# front_end_block.net
KiCad netlist of a schematic drawn in EAGLE
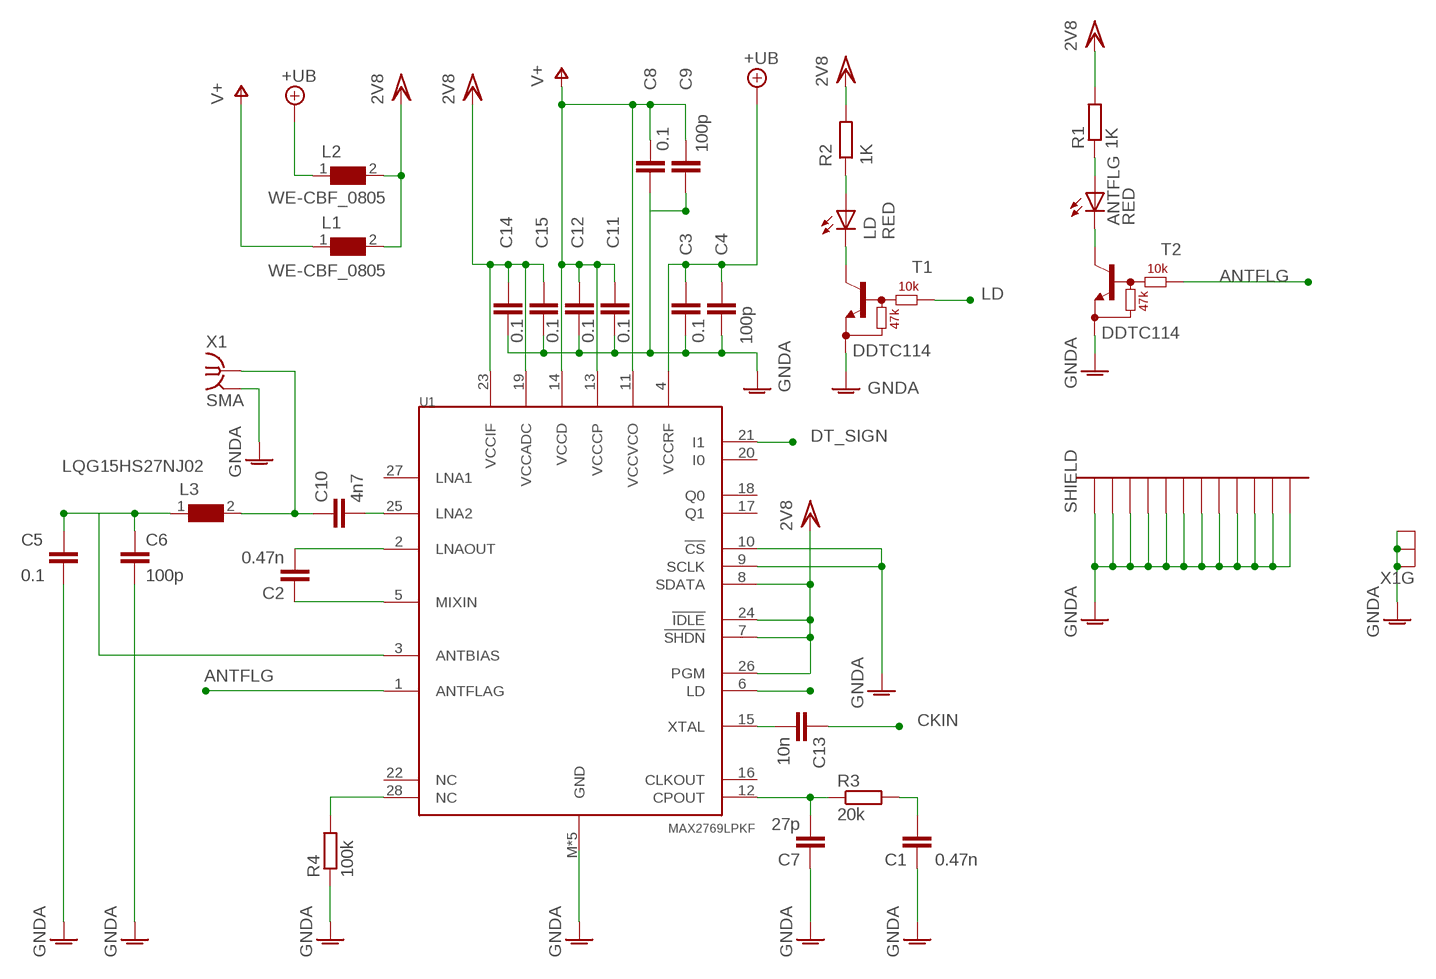
[diagram p0: schematic, sheet 1]

(export (version "E")
  (design (tool "Eeschema 10.0.6"))
  (components
    (comp (ref "ANTFLG")
      (value "RED")
      (footprint "eagle-import:CHIP-LED0603")
      (libsource (lib "eagle-import") (part "LEDCHIP-LED0603"))
    )
    (comp (ref "C1")
      (value "0.47n")
      (footprint "eagle-import:C0603")
      (libsource (lib "eagle-import") (part "rcl_1_C-EUC0603"))
    )
    (comp (ref "C2")
      (value "0.47n")
      (footprint "eagle-import:C0402")
      (libsource (lib "eagle-import") (part "rcl_1_C-EUC0402"))
    )
    (comp (ref "C3")
      (value "0.1")
      (footprint "eagle-import:C0402")
      (libsource (lib "eagle-import") (part "rcl_1_C-EUC0402"))
    )
    (comp (ref "C4")
      (value "100p")
      (footprint "eagle-import:C0402")
      (libsource (lib "eagle-import") (part "rcl_1_C-EUC0402"))
    )
    (comp (ref "C5")
      (value "0.1")
      (footprint "eagle-import:C0603")
      (libsource (lib "eagle-import") (part "C-EUC0603"))
    )
    (comp (ref "C6")
      (value "100p")
      (footprint "eagle-import:C0402")
      (libsource (lib "eagle-import") (part "rcl_1_C-EUC0402"))
    )
    (comp (ref "C7")
      (value "27p")
      (footprint "eagle-import:C0402")
      (libsource (lib "eagle-import") (part "rcl_1_C-EUC0402"))
    )
    (comp (ref "C8")
      (value "0.1")
      (footprint "eagle-import:C0402")
      (libsource (lib "eagle-import") (part "rcl_1_C-EUC0402"))
    )
    (comp (ref "C9")
      (value "100p")
      (footprint "eagle-import:C0402")
      (libsource (lib "eagle-import") (part "rcl_1_C-EUC0402"))
    )
    (comp (ref "C10")
      (value "4n7")
      (footprint "eagle-import:C0402")
      (libsource (lib "eagle-import") (part "rcl_1_C-EUC0402"))
    )
    (comp (ref "C11")
      (value "0.1")
      (footprint "eagle-import:C0402")
      (libsource (lib "eagle-import") (part "rcl_1_C-EUC0402"))
    )
    (comp (ref "C12")
      (value "0.1")
      (footprint "eagle-import:C0402")
      (libsource (lib "eagle-import") (part "rcl_1_C-EUC0402"))
    )
    (comp (ref "C13")
      (value "10n")
      (footprint "eagle-import:C0402")
      (libsource (lib "eagle-import") (part "rcl_1_C-EUC0402"))
    )
    (comp (ref "C14")
      (value "0.1")
      (footprint "eagle-import:C0603")
      (libsource (lib "eagle-import") (part "rcl_1_C-EUC0603"))
    )
    (comp (ref "C15")
      (value "0.1")
      (footprint "eagle-import:C0402")
      (libsource (lib "eagle-import") (part "rcl_1_C-EUC0402"))
    )
    (comp (ref "L1")
      (value "WE-CBF_0805")
      (footprint "eagle-import:0805")
      (libsource (lib "eagle-import") (part "WE-CBF_0805"))
    )
    (comp (ref "L2")
      (value "WE-CBF_0805")
      (footprint "eagle-import:0805")
      (libsource (lib "eagle-import") (part "WE-CBF_0805"))
    )
    (comp (ref "L3")
      (value "LQG15HS27NJ02")
      (footprint "eagle-import:0402")
      (libsource (lib "eagle-import") (part "WE-MK_0402"))
    )
    (comp (ref "LD")
      (value "RED")
      (footprint "eagle-import:CHIP-LED0603")
      (libsource (lib "eagle-import") (part "LEDCHIP-LED0603"))
    )
    (comp (ref "R1")
      (value "1K")
      (footprint "eagle-import:R0402")
      (libsource (lib "eagle-import") (part "R-EU_R0402"))
    )
    (comp (ref "R2")
      (value "1K")
      (footprint "eagle-import:R0402")
      (libsource (lib "eagle-import") (part "R-EU_R0402"))
    )
    (comp (ref "R3")
      (value "20k")
      (footprint "eagle-import:R0402")
      (libsource (lib "eagle-import") (part "R-EU_R0402"))
    )
    (comp (ref "R4")
      (value "100k")
      (footprint "eagle-import:R0402")
      (libsource (lib "eagle-import") (part "R-EU_R0402"))
    )
    (comp (ref "S2")
      (value "BMIS-202")
      (footprint "eagle-import:BMIS-202")
      (libsource (lib "eagle-import") (part "BMIS-202"))
    )
    (comp (ref "T1")
      (value "DDTC114")
      (footprint "eagle-import:SOT323-R_INFINEON")
      (libsource (lib "eagle-import") (part "BCR135W"))
    )
    (comp (ref "T2")
      (value "DDTC114")
      (footprint "eagle-import:SOT323-R_INFINEON")
      (libsource (lib "eagle-import") (part "BCR135W"))
    )
    (comp (ref "U1")
      (value "MAX2769LPKF")
      (footprint "eagle-import:QFN28LPKF")
      (libsource (lib "eagle-import") (part "MAX2769LPKF"))
    )
    (comp (ref "X1")
      (value "SMA")
      (footprint "eagle-import:J502-ND-142-0701-801_806")
      (fields (field (name "MF") "JOHNSON COMPONENTS") (field (name "MPN") "142-0701-801"))
      (libsource (lib "eagle-import") (part "SMA-142-0701-801/806"))
    )
  )
  (nets
    (net (code "1") (name "+UB") (class "Default")
      (node (ref "C3") (pin "1") (pinfunction "1_1") (pintype "passive"))
      (node (ref "C4") (pin "1") (pinfunction "1_1") (pintype "passive"))
      (node (ref "L2") (pin "1") (pinfunction "1_1") (pintype "passive"))
      (node (ref "U1") (pin "4") (pinfunction "VCCRF_4") (pintype "power_in"))
    )
    (net (code "2") (name "/ANTFLG") (class "Default")
      (node (ref "T2") (pin "1") (pinfunction "B_1") (pintype "passive"))
      (node (ref "U1") (pin "1") (pinfunction "ANTFLAG_1") (pintype "output"))
    )
    (net (code "3") (name "/CKIN") (class "Default")
      (node (ref "C13") (pin "1") (pinfunction "1_1") (pintype "passive"))
    )
    (net (code "4") (name "/DT_SIGN") (class "Default")
      (node (ref "U1") (pin "21") (pinfunction "I1_21") (pintype "output"))
    )
    (net (code "5") (name "/LD") (class "Default")
      (node (ref "T1") (pin "1") (pinfunction "B_1") (pintype "passive"))
      (node (ref "U1") (pin "6") (pinfunction "LD_6") (pintype "output"))
    )
    (net (code "6") (name "2V8") (class "Default")
      (node (ref "C14") (pin "1") (pinfunction "1_1") (pintype "passive"))
      (node (ref "C15") (pin "1") (pinfunction "1_1") (pintype "passive"))
      (node (ref "L1") (pin "2") (pinfunction "2_2") (pintype "passive"))
      (node (ref "L2") (pin "2") (pinfunction "2_2") (pintype "passive"))
      (node (ref "R1") (pin "2") (pinfunction "2_2") (pintype "passive"))
      (node (ref "R2") (pin "2") (pinfunction "2_2") (pintype "passive"))
      (node (ref "U1") (pin "19") (pinfunction "VCCADC_19") (pintype "power_in"))
      (node (ref "U1") (pin "23") (pinfunction "VCCIF_23") (pintype "power_in"))
      (node (ref "U1") (pin "24") (pinfunction "~{IDLE}_24") (pintype "input"))
      (node (ref "U1") (pin "26") (pinfunction "PGM_26") (pintype "input"))
      (node (ref "U1") (pin "7") (pinfunction "~{SHDN}_7") (pintype "input"))
      (node (ref "U1") (pin "8") (pinfunction "SDATA_8") (pintype "input"))
    )
    (net (code "7") (name "GNDA") (class "Default")
      (node (ref "C1") (pin "1") (pinfunction "1_1") (pintype "passive"))
      (node (ref "C11") (pin "2") (pinfunction "2_2") (pintype "passive"))
      (node (ref "C12") (pin "2") (pinfunction "2_2") (pintype "passive"))
      (node (ref "C14") (pin "2") (pinfunction "2_2") (pintype "passive"))
      (node (ref "C15") (pin "2") (pinfunction "2_2") (pintype "passive"))
      (node (ref "C3") (pin "2") (pinfunction "2_2") (pintype "passive"))
      (node (ref "C4") (pin "2") (pinfunction "2_2") (pintype "passive"))
      (node (ref "C5") (pin "2") (pinfunction "2_2") (pintype "passive"))
      (node (ref "C6") (pin "2") (pinfunction "2_2") (pintype "passive"))
      (node (ref "C7") (pin "1") (pinfunction "1_1") (pintype "passive"))
      (node (ref "C8") (pin "2") (pinfunction "2_2") (pintype "passive"))
      (node (ref "C9") (pin "2") (pinfunction "2_2") (pintype "passive"))
      (node (ref "R4") (pin "1") (pinfunction "1_1") (pintype "passive"))
      (node (ref "S2") (pin "P$1") (pinfunction "GND_P$1") (pintype "power_in"))
      (node (ref "S2") (pin "P$10") (pinfunction "GND_P$10") (pintype "power_in"))
      (node (ref "S2") (pin "P$11") (pinfunction "GND_P$11") (pintype "power_in"))
      (node (ref "S2") (pin "P$12") (pinfunction "GND_P$12") (pintype "power_in"))
      (node (ref "S2") (pin "P$2") (pinfunction "GND_P$2") (pintype "power_in"))
      (node (ref "S2") (pin "P$3") (pinfunction "GND_P$3") (pintype "power_in"))
      (node (ref "S2") (pin "P$4") (pinfunction "GND_P$4") (pintype "power_in"))
      (node (ref "S2") (pin "P$5") (pinfunction "GND_P$5") (pintype "power_in"))
      (node (ref "S2") (pin "P$6") (pinfunction "GND_P$6") (pintype "power_in"))
      (node (ref "S2") (pin "P$7") (pinfunction "GND_P$7") (pintype "power_in"))
      (node (ref "S2") (pin "P$8") (pinfunction "GND_P$8") (pintype "power_in"))
      (node (ref "S2") (pin "P$9") (pinfunction "GND_P$9") (pintype "power_in"))
      (node (ref "T1") (pin "2") (pinfunction "E_2") (pintype "passive"))
      (node (ref "T2") (pin "2") (pinfunction "E_2") (pintype "passive"))
      (node (ref "U1") (pin "10") (pinfunction "~{CS}_10") (pintype "input"))
      (node (ref "U1") (pin "9") (pinfunction "SCLK_9") (pintype "input"))
      (node (ref "U1") (pin "M") (pinfunction "GND_M") (pintype "power_in"))
      (node (ref "U1") (pin "P$4") (pinfunction "GND_P$4") (pintype "power_in"))
      (node (ref "U1") (pin "P$6") (pinfunction "GND_P$6") (pintype "power_in"))
      (node (ref "U1") (pin "P$7") (pinfunction "GND_P$7") (pintype "power_in"))
      (node (ref "U1") (pin "P$9") (pinfunction "GND_P$9") (pintype "power_in"))
      (node (ref "X1") (pin "G@1") (pinfunction "GND_G@1") (pintype "power_in"))
      (node (ref "X1") (pin "G@2") (pinfunction "GND_G@2") (pintype "power_in"))
      (node (ref "X1") (pin "G@3") (pinfunction "GND_G@3") (pintype "power_in"))
      (node (ref "X1") (pin "G@4") (pinfunction "GND_G@4") (pintype "power_in"))
    )
    (net (code "8") (name "Net-(ANTFLG-PadA)") (class "Default")
      (node (ref "ANTFLG") (pin "A") (pinfunction "A_A") (pintype "passive"))
      (node (ref "R1") (pin "1") (pinfunction "1_1") (pintype "passive"))
    )
    (net (code "9") (name "Net-(C1-Pad2)") (class "Default")
      (node (ref "C1") (pin "2") (pinfunction "2_2") (pintype "passive"))
      (node (ref "R3") (pin "2") (pinfunction "2_2") (pintype "passive"))
    )
    (net (code "10") (name "Net-(C10-Pad1)") (class "Default")
      (node (ref "C10") (pin "1") (pinfunction "1_1") (pintype "passive"))
      (node (ref "L3") (pin "2") (pinfunction "2_2") (pintype "passive"))
      (node (ref "X1") (pin "1") (pinfunction "1_1") (pintype "passive"))
    )
    (net (code "11") (name "Net-(LD-PadA)") (class "Default")
      (node (ref "LD") (pin "A") (pinfunction "A_A") (pintype "passive"))
      (node (ref "R2") (pin "1") (pinfunction "1_1") (pintype "passive"))
    )
    (net (code "12") (name "Net-(T1-C)") (class "Default")
      (node (ref "LD") (pin "C") (pinfunction "C_C") (pintype "passive"))
      (node (ref "T1") (pin "3") (pinfunction "C_3") (pintype "passive"))
    )
    (net (code "13") (name "Net-(T2-C)") (class "Default")
      (node (ref "ANTFLG") (pin "C") (pinfunction "C_C") (pintype "passive"))
      (node (ref "T2") (pin "3") (pinfunction "C_3") (pintype "passive"))
    )
    (net (code "14") (name "Net-(U1-ANTBIAS)") (class "Default")
      (node (ref "C5") (pin "1") (pinfunction "1_1") (pintype "passive"))
      (node (ref "C6") (pin "1") (pinfunction "1_1") (pintype "passive"))
      (node (ref "L3") (pin "1") (pinfunction "1_1") (pintype "passive"))
      (node (ref "U1") (pin "3") (pinfunction "ANTBIAS_3") (pintype "output"))
    )
    (net (code "15") (name "Net-(U1-CPOUT)") (class "Default")
      (node (ref "C7") (pin "2") (pinfunction "2_2") (pintype "passive"))
      (node (ref "R3") (pin "1") (pinfunction "1_1") (pintype "passive"))
      (node (ref "U1") (pin "12") (pinfunction "CPOUT_12") (pintype "output"))
    )
    (net (code "16") (name "Net-(U1-LNA2)") (class "Default")
      (node (ref "C10") (pin "2") (pinfunction "2_2") (pintype "passive"))
      (node (ref "U1") (pin "25") (pinfunction "LNA2_25") (pintype "input"))
    )
    (net (code "17") (name "Net-(U1-LNAOUT)") (class "Default")
      (node (ref "C2") (pin "2") (pinfunction "2_2") (pintype "passive"))
      (node (ref "U1") (pin "2") (pinfunction "LNAOUT_2") (pintype "output"))
    )
    (net (code "18") (name "Net-(U1-MIXIN)") (class "Default")
      (node (ref "C2") (pin "1") (pinfunction "1_1") (pintype "passive"))
      (node (ref "U1") (pin "5") (pinfunction "MIXIN_5") (pintype "input"))
    )
    (net (code "19") (name "Net-(U1-NC)") (class "Default")
      (node (ref "R4") (pin "2") (pinfunction "2_2") (pintype "passive"))
      (node (ref "U1") (pin "28") (pinfunction "NC_28") (pintype "output"))
    )
    (net (code "20") (name "Net-(U1-XTAL)") (class "Default")
      (node (ref "C13") (pin "2") (pinfunction "2_2") (pintype "passive"))
      (node (ref "U1") (pin "15") (pinfunction "XTAL_15") (pintype "input"))
    )
    (net (code "21") (name "V+") (class "Default")
      (node (ref "C11") (pin "1") (pinfunction "1_1") (pintype "passive"))
      (node (ref "C12") (pin "1") (pinfunction "1_1") (pintype "passive"))
      (node (ref "C8") (pin "1") (pinfunction "1_1") (pintype "passive"))
      (node (ref "C9") (pin "1") (pinfunction "1_1") (pintype "passive"))
      (node (ref "L1") (pin "1") (pinfunction "1_1") (pintype "passive"))
      (node (ref "U1") (pin "11") (pinfunction "VCCVCO_11") (pintype "power_in"))
      (node (ref "U1") (pin "13") (pinfunction "VCCCP_13") (pintype "power_in"))
      (node (ref "U1") (pin "14") (pinfunction "VCCD_14") (pintype "power_in"))
    )
    (net (code "22") (name "unconnected-(U1-CLKOUT-Pad16)") (class "Default")
      (node (ref "U1") (pin "16") (pinfunction "CLKOUT_16") (pintype "output"))
    )
    (net (code "23") (name "unconnected-(U1-I0-Pad20)") (class "Default")
      (node (ref "U1") (pin "20") (pinfunction "I0_20") (pintype "output"))
    )
    (net (code "24") (name "unconnected-(U1-LNA1-Pad27)") (class "Default")
      (node (ref "U1") (pin "27") (pinfunction "LNA1_27") (pintype "input"))
    )
    (net (code "25") (name "unconnected-(U1-NC-Pad22)") (class "Default")
      (node (ref "U1") (pin "22") (pinfunction "NC_22") (pintype "no_connect"))
    )
    (net (code "26") (name "unconnected-(U1-Q0-Pad18)") (class "Default")
      (node (ref "U1") (pin "18") (pinfunction "Q0_18") (pintype "output"))
    )
    (net (code "27") (name "unconnected-(U1-Q1-Pad17)") (class "Default")
      (node (ref "U1") (pin "17") (pinfunction "Q1_17") (pintype "output"))
    )
  )
)
